# high_current_motor_controller.net
KiCad netlist of a schematic drawn in EAGLE
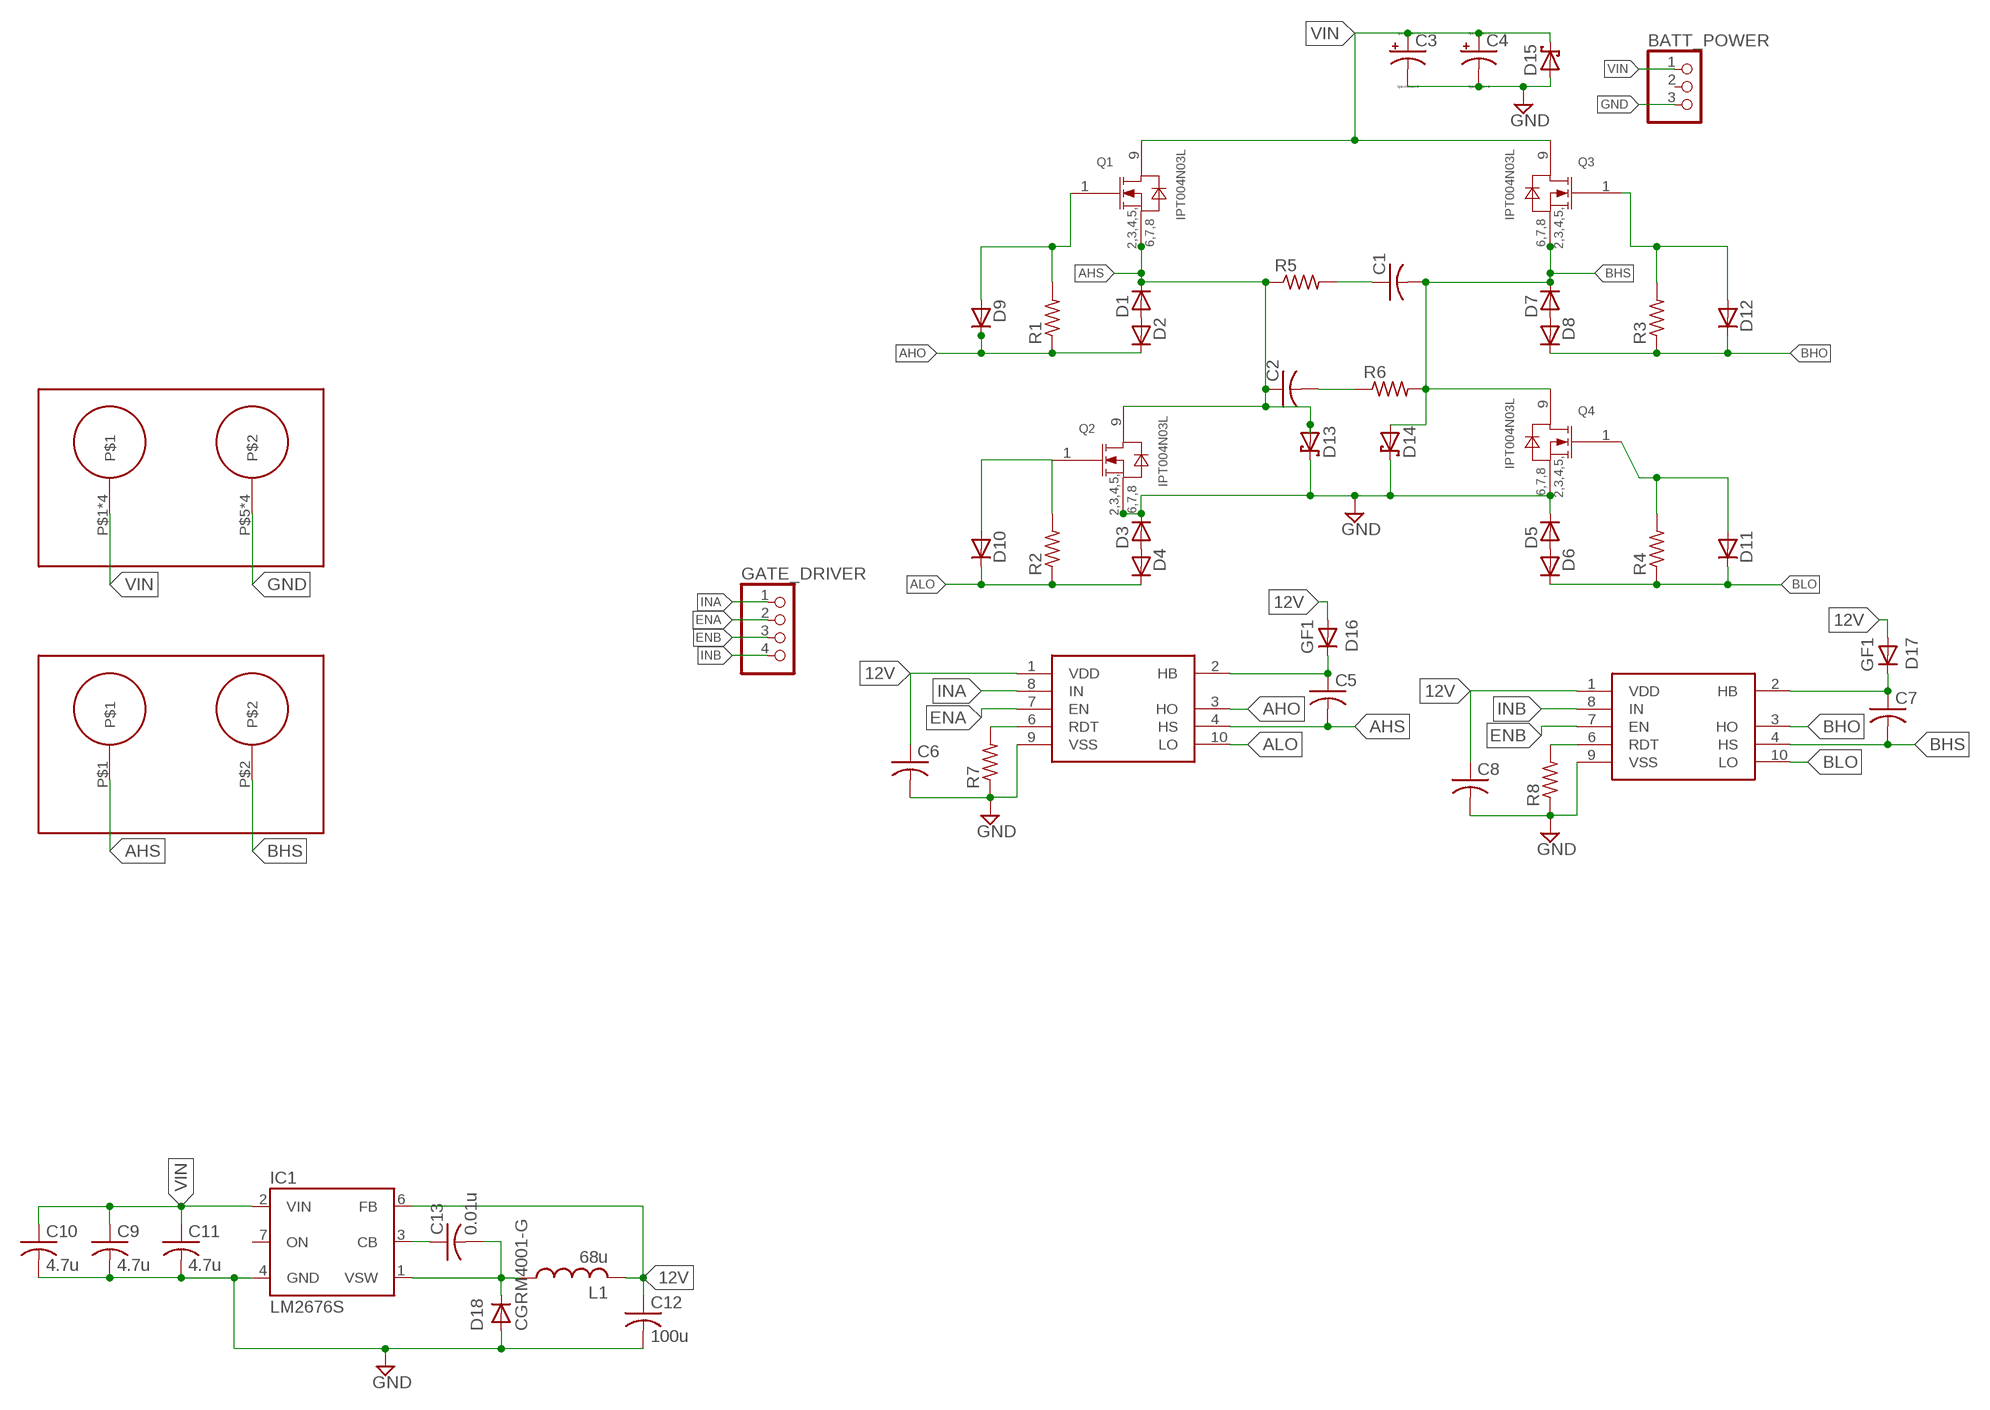
[diagram p0: schematic, sheet 1]

(export (version "E")
  (design (tool "Eeschema 10.0.6"))
  (components
    (comp (ref "BATT_POWER")
      (value "PINHD-1X3")
      (footprint "eagle-import:1X03")
      (libsource (lib "eagle-import") (part "PINHD-1X3"))
    )
    (comp (ref "C1")
      (value "C-USC0805")
      (footprint "eagle-import:C0805")
      (libsource (lib "eagle-import") (part "C-USC0805"))
    )
    (comp (ref "C2")
      (value "C-USC0805")
      (footprint "eagle-import:C0805")
      (libsource (lib "eagle-import") (part "C-USC0805"))
    )
    (comp (ref "C3")
      (value "CPOL-USE5-13")
      (footprint "eagle-import:E5-13")
      (libsource (lib "eagle-import") (part "CPOL-USE5-13"))
    )
    (comp (ref "C4")
      (value "CPOL-USE5-13")
      (footprint "eagle-import:E5-13")
      (libsource (lib "eagle-import") (part "CPOL-USE5-13"))
    )
    (comp (ref "C5")
      (value "C-USC0805")
      (footprint "eagle-import:C0805")
      (libsource (lib "eagle-import") (part "C-USC0805"))
    )
    (comp (ref "C6")
      (value "C-USC0805")
      (footprint "eagle-import:C0805")
      (libsource (lib "eagle-import") (part "C-USC0805"))
    )
    (comp (ref "C7")
      (value "C-USC0805")
      (footprint "eagle-import:C0805")
      (libsource (lib "eagle-import") (part "C-USC0805"))
    )
    (comp (ref "C8")
      (value "C-USC0805")
      (footprint "eagle-import:C0805")
      (libsource (lib "eagle-import") (part "C-USC0805"))
    )
    (comp (ref "C9")
      (value "4.7u")
      (footprint "eagle-import:C0805")
      (libsource (lib "eagle-import") (part "C-USC0805"))
    )
    (comp (ref "C10")
      (value "4.7u")
      (footprint "eagle-import:C0805")
      (libsource (lib "eagle-import") (part "C-USC0805"))
    )
    (comp (ref "C11")
      (value "4.7u")
      (footprint "eagle-import:C0805")
      (libsource (lib "eagle-import") (part "C-USC0805"))
    )
    (comp (ref "C12")
      (value "100u")
      (footprint "eagle-import:C0805")
      (libsource (lib "eagle-import") (part "C-USC0805"))
    )
    (comp (ref "C13")
      (value "0.01u")
      (footprint "eagle-import:C0805")
      (libsource (lib "eagle-import") (part "C-USC0805"))
    )
    (comp (ref "D1")
      (value "D-SOD123")
      (footprint "eagle-import:SOD123")
      (libsource (lib "eagle-import") (part "D-SOD123"))
    )
    (comp (ref "D2")
      (value "D-SOD123")
      (footprint "eagle-import:SOD123")
      (libsource (lib "eagle-import") (part "D-SOD123"))
    )
    (comp (ref "D3")
      (value "D-SOD123")
      (footprint "eagle-import:SOD123")
      (libsource (lib "eagle-import") (part "D-SOD123"))
    )
    (comp (ref "D4")
      (value "D-SOD123")
      (footprint "eagle-import:SOD123")
      (libsource (lib "eagle-import") (part "D-SOD123"))
    )
    (comp (ref "D5")
      (value "D-SOD123")
      (footprint "eagle-import:SOD123")
      (libsource (lib "eagle-import") (part "D-SOD123"))
    )
    (comp (ref "D6")
      (value "D-SOD123")
      (footprint "eagle-import:SOD123")
      (libsource (lib "eagle-import") (part "D-SOD123"))
    )
    (comp (ref "D7")
      (value "D-SOD123")
      (footprint "eagle-import:SOD123")
      (libsource (lib "eagle-import") (part "D-SOD123"))
    )
    (comp (ref "D8")
      (value "D-SOD123")
      (footprint "eagle-import:SOD123")
      (libsource (lib "eagle-import") (part "D-SOD123"))
    )
    (comp (ref "D9")
      (value "D-SOD123")
      (footprint "eagle-import:SOD123")
      (libsource (lib "eagle-import") (part "D-SOD123"))
    )
    (comp (ref "D10")
      (value "D-SOD123")
      (footprint "eagle-import:SOD123")
      (libsource (lib "eagle-import") (part "D-SOD123"))
    )
    (comp (ref "D11")
      (value "D-SOD123")
      (footprint "eagle-import:SOD123")
      (libsource (lib "eagle-import") (part "D-SOD123"))
    )
    (comp (ref "D12")
      (value "D-SOD123")
      (footprint "eagle-import:SOD123")
      (libsource (lib "eagle-import") (part "D-SOD123"))
    )
    (comp (ref "D13")
      (value "SCHOTTKY-DIODESMC")
      (footprint "eagle-import:SMC")
      (libsource (lib "eagle-import") (part "SCHOTTKY-DIODESMC"))
    )
    (comp (ref "D14")
      (value "SCHOTTKY-DIODESMC")
      (footprint "eagle-import:SMC")
      (libsource (lib "eagle-import") (part "SCHOTTKY-DIODESMC"))
    )
    (comp (ref "D15")
      (value "SCHOTTKY-DIODESMC")
      (footprint "eagle-import:SMC")
      (libsource (lib "eagle-import") (part "SCHOTTKY-DIODESMC"))
    )
    (comp (ref "D16")
      (value "GF1")
      (footprint "eagle-import:SMA-DO214AC")
      (libsource (lib "eagle-import") (part "GF1"))
    )
    (comp (ref "D17")
      (value "GF1")
      (footprint "eagle-import:SMA-DO214AC")
      (libsource (lib "eagle-import") (part "GF1"))
    )
    (comp (ref "D18")
      (value "CGRM4001-G")
      (footprint "eagle-import:SMA-DO214AC")
      (libsource (lib "eagle-import") (part "GF1"))
    )
    (comp (ref "GATE_DRIVER")
      (value "PINHD-1X4")
      (footprint "eagle-import:1X04")
      (libsource (lib "eagle-import") (part "PINHD-1X4"))
    )
    (comp (ref "IC1")
      (value "LM2676S")
      (footprint "eagle-import:TO263-7")
      (libsource (lib "eagle-import") (part "LM2676S"))
    )
    (comp (ref "L1")
      (value "68u")
      (footprint "eagle-import:L_WURTH_7447709680")
      (libsource (lib "eagle-import") (part "L-US12.8X12.8WURTH"))
    )
    (comp (ref "Q1")
      (value "IPT004N03L")
      (footprint "eagle-import:INF-PG-HSOF-8-1-0")
      (libsource (lib "eagle-import") (part "IPT004N03L"))
    )
    (comp (ref "Q2")
      (value "IPT004N03L")
      (footprint "eagle-import:INF-PG-HSOF-8-1-0")
      (libsource (lib "eagle-import") (part "IPT004N03L"))
    )
    (comp (ref "Q3")
      (value "IPT004N03L")
      (footprint "eagle-import:INF-PG-HSOF-8-1-0")
      (libsource (lib "eagle-import") (part "IPT004N03L"))
    )
    (comp (ref "Q4")
      (value "IPT004N03L")
      (footprint "eagle-import:INF-PG-HSOF-8-1-0")
      (libsource (lib "eagle-import") (part "IPT004N03L"))
    )
    (comp (ref "R1")
      (value "R-US_M0805")
      (footprint "eagle-import:M0805")
      (libsource (lib "eagle-import") (part "R-US_M0805"))
    )
    (comp (ref "R2")
      (value "R-US_M0805")
      (footprint "eagle-import:M0805")
      (libsource (lib "eagle-import") (part "R-US_M0805"))
    )
    (comp (ref "R3")
      (value "R-US_M0805")
      (footprint "eagle-import:M0805")
      (libsource (lib "eagle-import") (part "R-US_M0805"))
    )
    (comp (ref "R4")
      (value "R-US_M0805")
      (footprint "eagle-import:M0805")
      (libsource (lib "eagle-import") (part "R-US_M0805"))
    )
    (comp (ref "R5")
      (value "R-US_M0805")
      (footprint "eagle-import:M0805")
      (libsource (lib "eagle-import") (part "R-US_M0805"))
    )
    (comp (ref "R6")
      (value "R-US_M0805")
      (footprint "eagle-import:M0805")
      (libsource (lib "eagle-import") (part "R-US_M0805"))
    )
    (comp (ref "R7")
      (value "R-US_M0805")
      (footprint "eagle-import:M0805")
      (libsource (lib "eagle-import") (part "R-US_M0805"))
    )
    (comp (ref "R8")
      (value "R-US_M0805")
      (footprint "eagle-import:M0805")
      (libsource (lib "eagle-import") (part "R-US_M0805"))
    )
    (comp (ref "U$1")
      (value "LM5106MM")
      (footprint "eagle-import:MSOP10")
      (libsource (lib "eagle-import") (part "LM5106MM"))
    )
    (comp (ref "U$2")
      (value "LM5106MM")
      (footprint "eagle-import:MSOP10")
      (libsource (lib "eagle-import") (part "LM5106MM"))
    )
    (comp (ref "U$3")
      (value "TE_2PIN_125A")
      (footprint "eagle-import:TE_125A")
      (libsource (lib "eagle-import") (part "TE_2PIN_125A"))
    )
    (comp (ref "U$4")
      (value "MOLEX_2PIN_50A")
      (footprint "eagle-import:MOLEX_50A")
      (libsource (lib "eagle-import") (part "MOLEX_2PIN_50A"))
    )
  )
  (nets
    (net (code "1") (name "12V") (class "Default")
      (node (ref "C12") (pin "1") (pinfunction "1_1") (pintype "passive"))
      (node (ref "C6") (pin "1") (pinfunction "1_1") (pintype "passive"))
      (node (ref "C8") (pin "1") (pinfunction "1_1") (pintype "passive"))
      (node (ref "D16") (pin "A") (pinfunction "A_A") (pintype "passive"))
      (node (ref "D17") (pin "A") (pinfunction "A_A") (pintype "passive"))
      (node (ref "IC1") (pin "6") (pinfunction "FB_6") (pintype "input"))
      (node (ref "L1") (pin "P$2") (pinfunction "2_P$2") (pintype "passive"))
      (node (ref "U$1") (pin "1") (pinfunction "VDD_1") (pintype "bidirectional"))
      (node (ref "U$2") (pin "1") (pinfunction "VDD_1") (pintype "bidirectional"))
    )
    (net (code "2") (name "AHO") (class "Default")
      (node (ref "D2") (pin "1") (pinfunction "C_1") (pintype "passive"))
      (node (ref "D9") (pin "1") (pinfunction "C_1") (pintype "passive"))
      (node (ref "R1") (pin "1") (pinfunction "1_1") (pintype "passive"))
      (node (ref "U$1") (pin "3") (pinfunction "HO_3") (pintype "bidirectional"))
    )
    (net (code "3") (name "AHS") (class "Default")
      (node (ref "C2") (pin "1") (pinfunction "1_1") (pintype "passive"))
      (node (ref "C5") (pin "2") (pinfunction "2_2") (pintype "passive"))
      (node (ref "D1") (pin "1") (pinfunction "C_1") (pintype "passive"))
      (node (ref "D13") (pin "A") (pinfunction "A_A") (pintype "passive"))
      (node (ref "Q1") (pin "2") (pinfunction "2_2") (pintype "passive"))
      (node (ref "Q1") (pin "3") (pinfunction "3_3") (pintype "passive"))
      (node (ref "Q1") (pin "4") (pinfunction "4_4") (pintype "passive"))
      (node (ref "Q1") (pin "5") (pinfunction "5_5") (pintype "passive"))
      (node (ref "Q1") (pin "6") (pinfunction "6_6") (pintype "passive"))
      (node (ref "Q1") (pin "7") (pinfunction "7_7") (pintype "passive"))
      (node (ref "Q1") (pin "8") (pinfunction "8_8") (pintype "passive"))
      (node (ref "Q2") (pin "9") (pinfunction "9_9") (pintype "passive"))
      (node (ref "R5") (pin "1") (pinfunction "1_1") (pintype "passive"))
      (node (ref "U$1") (pin "4") (pinfunction "HS_4") (pintype "bidirectional"))
      (node (ref "U$4") (pin "P$1") (pinfunction "P$1_P$1") (pintype "bidirectional"))
    )
    (net (code "4") (name "ALO") (class "Default")
      (node (ref "D10") (pin "1") (pinfunction "C_1") (pintype "passive"))
      (node (ref "D4") (pin "1") (pinfunction "C_1") (pintype "passive"))
      (node (ref "R2") (pin "1") (pinfunction "1_1") (pintype "passive"))
      (node (ref "U$1") (pin "10") (pinfunction "LO_10") (pintype "bidirectional"))
    )
    (net (code "5") (name "BHO") (class "Default")
      (node (ref "D12") (pin "1") (pinfunction "C_1") (pintype "passive"))
      (node (ref "D8") (pin "1") (pinfunction "C_1") (pintype "passive"))
      (node (ref "R3") (pin "1") (pinfunction "1_1") (pintype "passive"))
      (node (ref "U$2") (pin "3") (pinfunction "HO_3") (pintype "bidirectional"))
    )
    (net (code "6") (name "BHS") (class "Default")
      (node (ref "C1") (pin "2") (pinfunction "2_2") (pintype "passive"))
      (node (ref "C7") (pin "2") (pinfunction "2_2") (pintype "passive"))
      (node (ref "D14") (pin "A") (pinfunction "A_A") (pintype "passive"))
      (node (ref "D7") (pin "1") (pinfunction "C_1") (pintype "passive"))
      (node (ref "Q3") (pin "2") (pinfunction "2_2") (pintype "passive"))
      (node (ref "Q3") (pin "3") (pinfunction "3_3") (pintype "passive"))
      (node (ref "Q3") (pin "4") (pinfunction "4_4") (pintype "passive"))
      (node (ref "Q3") (pin "5") (pinfunction "5_5") (pintype "passive"))
      (node (ref "Q3") (pin "6") (pinfunction "6_6") (pintype "passive"))
      (node (ref "Q3") (pin "7") (pinfunction "7_7") (pintype "passive"))
      (node (ref "Q3") (pin "8") (pinfunction "8_8") (pintype "passive"))
      (node (ref "Q4") (pin "9") (pinfunction "9_9") (pintype "passive"))
      (node (ref "R6") (pin "2") (pinfunction "2_2") (pintype "passive"))
      (node (ref "U$2") (pin "4") (pinfunction "HS_4") (pintype "bidirectional"))
      (node (ref "U$4") (pin "P$2") (pinfunction "P$2_P$2") (pintype "bidirectional"))
    )
    (net (code "7") (name "BLO") (class "Default")
      (node (ref "D11") (pin "1") (pinfunction "C_1") (pintype "passive"))
      (node (ref "D6") (pin "1") (pinfunction "C_1") (pintype "passive"))
      (node (ref "R4") (pin "1") (pinfunction "1_1") (pintype "passive"))
      (node (ref "U$2") (pin "10") (pinfunction "LO_10") (pintype "bidirectional"))
    )
    (net (code "8") (name "ENA") (class "Default")
      (node (ref "GATE_DRIVER") (pin "2") (pinfunction "2_2") (pintype "passive"))
      (node (ref "U$1") (pin "7") (pinfunction "EN_7") (pintype "bidirectional"))
    )
    (net (code "9") (name "ENB") (class "Default")
      (node (ref "GATE_DRIVER") (pin "3") (pinfunction "3_3") (pintype "passive"))
      (node (ref "U$2") (pin "7") (pinfunction "EN_7") (pintype "bidirectional"))
    )
    (net (code "10") (name "GND") (class "Default")
      (node (ref "BATT_POWER") (pin "3") (pinfunction "3_3") (pintype "passive"))
      (node (ref "C10") (pin "2") (pinfunction "2_2") (pintype "passive"))
      (node (ref "C11") (pin "2") (pinfunction "2_2") (pintype "passive"))
      (node (ref "C12") (pin "2") (pinfunction "2_2") (pintype "passive"))
      (node (ref "C3") (pin "-") (pinfunction "-_-") (pintype "passive"))
      (node (ref "C4") (pin "-") (pinfunction "-_-") (pintype "passive"))
      (node (ref "C6") (pin "2") (pinfunction "2_2") (pintype "passive"))
      (node (ref "C8") (pin "2") (pinfunction "2_2") (pintype "passive"))
      (node (ref "C9") (pin "2") (pinfunction "2_2") (pintype "passive"))
      (node (ref "D13") (pin "C") (pinfunction "C_C") (pintype "passive"))
      (node (ref "D14") (pin "C") (pinfunction "C_C") (pintype "passive"))
      (node (ref "D15") (pin "A") (pinfunction "A_A") (pintype "passive"))
      (node (ref "D18") (pin "A") (pinfunction "A_A") (pintype "passive"))
      (node (ref "D3") (pin "1") (pinfunction "C_1") (pintype "passive"))
      (node (ref "D5") (pin "1") (pinfunction "C_1") (pintype "passive"))
      (node (ref "IC1") (pin "4") (pinfunction "GND_4") (pintype "power_in"))
      (node (ref "Q2") (pin "2") (pinfunction "2_2") (pintype "passive"))
      (node (ref "Q2") (pin "3") (pinfunction "3_3") (pintype "passive"))
      (node (ref "Q2") (pin "4") (pinfunction "4_4") (pintype "passive"))
      (node (ref "Q2") (pin "5") (pinfunction "5_5") (pintype "passive"))
      (node (ref "Q2") (pin "6") (pinfunction "6_6") (pintype "passive"))
      (node (ref "Q2") (pin "7") (pinfunction "7_7") (pintype "passive"))
      (node (ref "Q2") (pin "8") (pinfunction "8_8") (pintype "passive"))
      (node (ref "Q4") (pin "2") (pinfunction "2_2") (pintype "passive"))
      (node (ref "Q4") (pin "3") (pinfunction "3_3") (pintype "passive"))
      (node (ref "Q4") (pin "4") (pinfunction "4_4") (pintype "passive"))
      (node (ref "Q4") (pin "5") (pinfunction "5_5") (pintype "passive"))
      (node (ref "Q4") (pin "6") (pinfunction "6_6") (pintype "passive"))
      (node (ref "Q4") (pin "7") (pinfunction "7_7") (pintype "passive"))
      (node (ref "Q4") (pin "8") (pinfunction "8_8") (pintype "passive"))
      (node (ref "R7") (pin "1") (pinfunction "1_1") (pintype "passive"))
      (node (ref "R8") (pin "1") (pinfunction "1_1") (pintype "passive"))
      (node (ref "U$1") (pin "9") (pinfunction "VSS_9") (pintype "bidirectional"))
      (node (ref "U$2") (pin "9") (pinfunction "VSS_9") (pintype "bidirectional"))
      (node (ref "U$3") (pin "P$5") (pinfunction "P$2_P$5") (pintype "bidirectional"))
      (node (ref "U$3") (pin "P$6") (pinfunction "P$2_P$6") (pintype "bidirectional"))
      (node (ref "U$3") (pin "P$7") (pinfunction "P$2_P$7") (pintype "bidirectional"))
      (node (ref "U$3") (pin "P$8") (pinfunction "P$2_P$8") (pintype "bidirectional"))
    )
    (net (code "11") (name "INA") (class "Default")
      (node (ref "GATE_DRIVER") (pin "1") (pinfunction "1_1") (pintype "passive"))
      (node (ref "U$1") (pin "8") (pinfunction "IN_8") (pintype "bidirectional"))
    )
    (net (code "12") (name "INB") (class "Default")
      (node (ref "GATE_DRIVER") (pin "4") (pinfunction "4_4") (pintype "passive"))
      (node (ref "U$2") (pin "8") (pinfunction "IN_8") (pintype "bidirectional"))
    )
    (net (code "13") (name "Net-(C1-Pad1)") (class "Default")
      (node (ref "C1") (pin "1") (pinfunction "1_1") (pintype "passive"))
      (node (ref "R5") (pin "2") (pinfunction "2_2") (pintype "passive"))
    )
    (net (code "14") (name "Net-(C2-Pad2)") (class "Default")
      (node (ref "C2") (pin "2") (pinfunction "2_2") (pintype "passive"))
      (node (ref "R6") (pin "1") (pinfunction "1_1") (pintype "passive"))
    )
    (net (code "15") (name "Net-(D1-A)") (class "Default")
      (node (ref "D1") (pin "2") (pinfunction "A_2") (pintype "passive"))
      (node (ref "D2") (pin "2") (pinfunction "A_2") (pintype "passive"))
    )
    (net (code "16") (name "Net-(D3-A)") (class "Default")
      (node (ref "D3") (pin "2") (pinfunction "A_2") (pintype "passive"))
      (node (ref "D4") (pin "2") (pinfunction "A_2") (pintype "passive"))
    )
    (net (code "17") (name "Net-(D5-A)") (class "Default")
      (node (ref "D5") (pin "2") (pinfunction "A_2") (pintype "passive"))
      (node (ref "D6") (pin "2") (pinfunction "A_2") (pintype "passive"))
    )
    (net (code "18") (name "Net-(D7-A)") (class "Default")
      (node (ref "D7") (pin "2") (pinfunction "A_2") (pintype "passive"))
      (node (ref "D8") (pin "2") (pinfunction "A_2") (pintype "passive"))
    )
    (net (code "19") (name "Net-(D9-A)") (class "Default")
      (node (ref "D9") (pin "2") (pinfunction "A_2") (pintype "passive"))
      (node (ref "Q1") (pin "1") (pinfunction "1_1") (pintype "passive"))
      (node (ref "R1") (pin "2") (pinfunction "2_2") (pintype "passive"))
    )
    (net (code "20") (name "Net-(D10-A)") (class "Default")
      (node (ref "D10") (pin "2") (pinfunction "A_2") (pintype "passive"))
      (node (ref "Q2") (pin "1") (pinfunction "1_1") (pintype "passive"))
      (node (ref "R2") (pin "2") (pinfunction "2_2") (pintype "passive"))
    )
    (net (code "21") (name "Net-(D11-A)") (class "Default")
      (node (ref "D11") (pin "2") (pinfunction "A_2") (pintype "passive"))
      (node (ref "Q4") (pin "1") (pinfunction "1_1") (pintype "passive"))
      (node (ref "R4") (pin "2") (pinfunction "2_2") (pintype "passive"))
    )
    (net (code "22") (name "Net-(D12-A)") (class "Default")
      (node (ref "D12") (pin "2") (pinfunction "A_2") (pintype "passive"))
      (node (ref "Q3") (pin "1") (pinfunction "1_1") (pintype "passive"))
      (node (ref "R3") (pin "2") (pinfunction "2_2") (pintype "passive"))
    )
    (net (code "23") (name "Net-(D16-C)") (class "Default")
      (node (ref "C5") (pin "1") (pinfunction "1_1") (pintype "passive"))
      (node (ref "D16") (pin "K") (pinfunction "C_K") (pintype "passive"))
      (node (ref "U$1") (pin "2") (pinfunction "HB_2") (pintype "bidirectional"))
    )
    (net (code "24") (name "Net-(D17-C)") (class "Default")
      (node (ref "C7") (pin "1") (pinfunction "1_1") (pintype "passive"))
      (node (ref "D17") (pin "K") (pinfunction "C_K") (pintype "passive"))
      (node (ref "U$2") (pin "2") (pinfunction "HB_2") (pintype "bidirectional"))
    )
    (net (code "25") (name "Net-(D18-C)") (class "Default")
      (node (ref "C13") (pin "2") (pinfunction "2_2") (pintype "passive"))
      (node (ref "D18") (pin "K") (pinfunction "C_K") (pintype "passive"))
      (node (ref "IC1") (pin "1") (pinfunction "VSW_1") (pintype "output"))
      (node (ref "L1") (pin "P$1") (pinfunction "1_P$1") (pintype "passive"))
    )
    (net (code "26") (name "Net-(IC1-CB)") (class "Default")
      (node (ref "C13") (pin "1") (pinfunction "1_1") (pintype "passive"))
      (node (ref "IC1") (pin "3") (pinfunction "CB_3") (pintype "input"))
    )
    (net (code "27") (name "Net-(U$1-RDT)") (class "Default")
      (node (ref "R7") (pin "2") (pinfunction "2_2") (pintype "passive"))
      (node (ref "U$1") (pin "6") (pinfunction "RDT_6") (pintype "bidirectional"))
    )
    (net (code "28") (name "Net-(U$2-RDT)") (class "Default")
      (node (ref "R8") (pin "2") (pinfunction "2_2") (pintype "passive"))
      (node (ref "U$2") (pin "6") (pinfunction "RDT_6") (pintype "bidirectional"))
    )
    (net (code "29") (name "VIN") (class "Default")
      (node (ref "BATT_POWER") (pin "1") (pinfunction "1_1") (pintype "passive"))
      (node (ref "C10") (pin "1") (pinfunction "1_1") (pintype "passive"))
      (node (ref "C11") (pin "1") (pinfunction "1_1") (pintype "passive"))
      (node (ref "C3") (pin "+") (pinfunction "+_+") (pintype "passive"))
      (node (ref "C4") (pin "+") (pinfunction "+_+") (pintype "passive"))
      (node (ref "C9") (pin "1") (pinfunction "1_1") (pintype "passive"))
      (node (ref "D15") (pin "C") (pinfunction "C_C") (pintype "passive"))
      (node (ref "IC1") (pin "2") (pinfunction "VIN_2") (pintype "power_in"))
      (node (ref "Q1") (pin "9") (pinfunction "9_9") (pintype "passive"))
      (node (ref "Q3") (pin "9") (pinfunction "9_9") (pintype "passive"))
      (node (ref "U$3") (pin "P$1") (pinfunction "P$1_P$1") (pintype "bidirectional"))
      (node (ref "U$3") (pin "P$1.1") (pinfunction "P$1_P$1.1") (pintype "bidirectional"))
      (node (ref "U$3") (pin "P$1.2") (pinfunction "P$1_P$1.2") (pintype "bidirectional"))
      (node (ref "U$3") (pin "P$1.3") (pinfunction "P$1_P$1.3") (pintype "bidirectional"))
    )
    (net (code "30") (name "unconnected-(BATT_POWER-Pad2)") (class "Default")
      (node (ref "BATT_POWER") (pin "2") (pinfunction "2_2") (pintype "passive"))
    )
    (net (code "31") (name "unconnected-(IC1-ON-Pad7)") (class "Default")
      (node (ref "IC1") (pin "7") (pinfunction "ON_7") (pintype "passive"))
    )
  )
)
